# 3_3_5_12.net
KiCad netlist of a schematic drawn in EasyEDA Pro
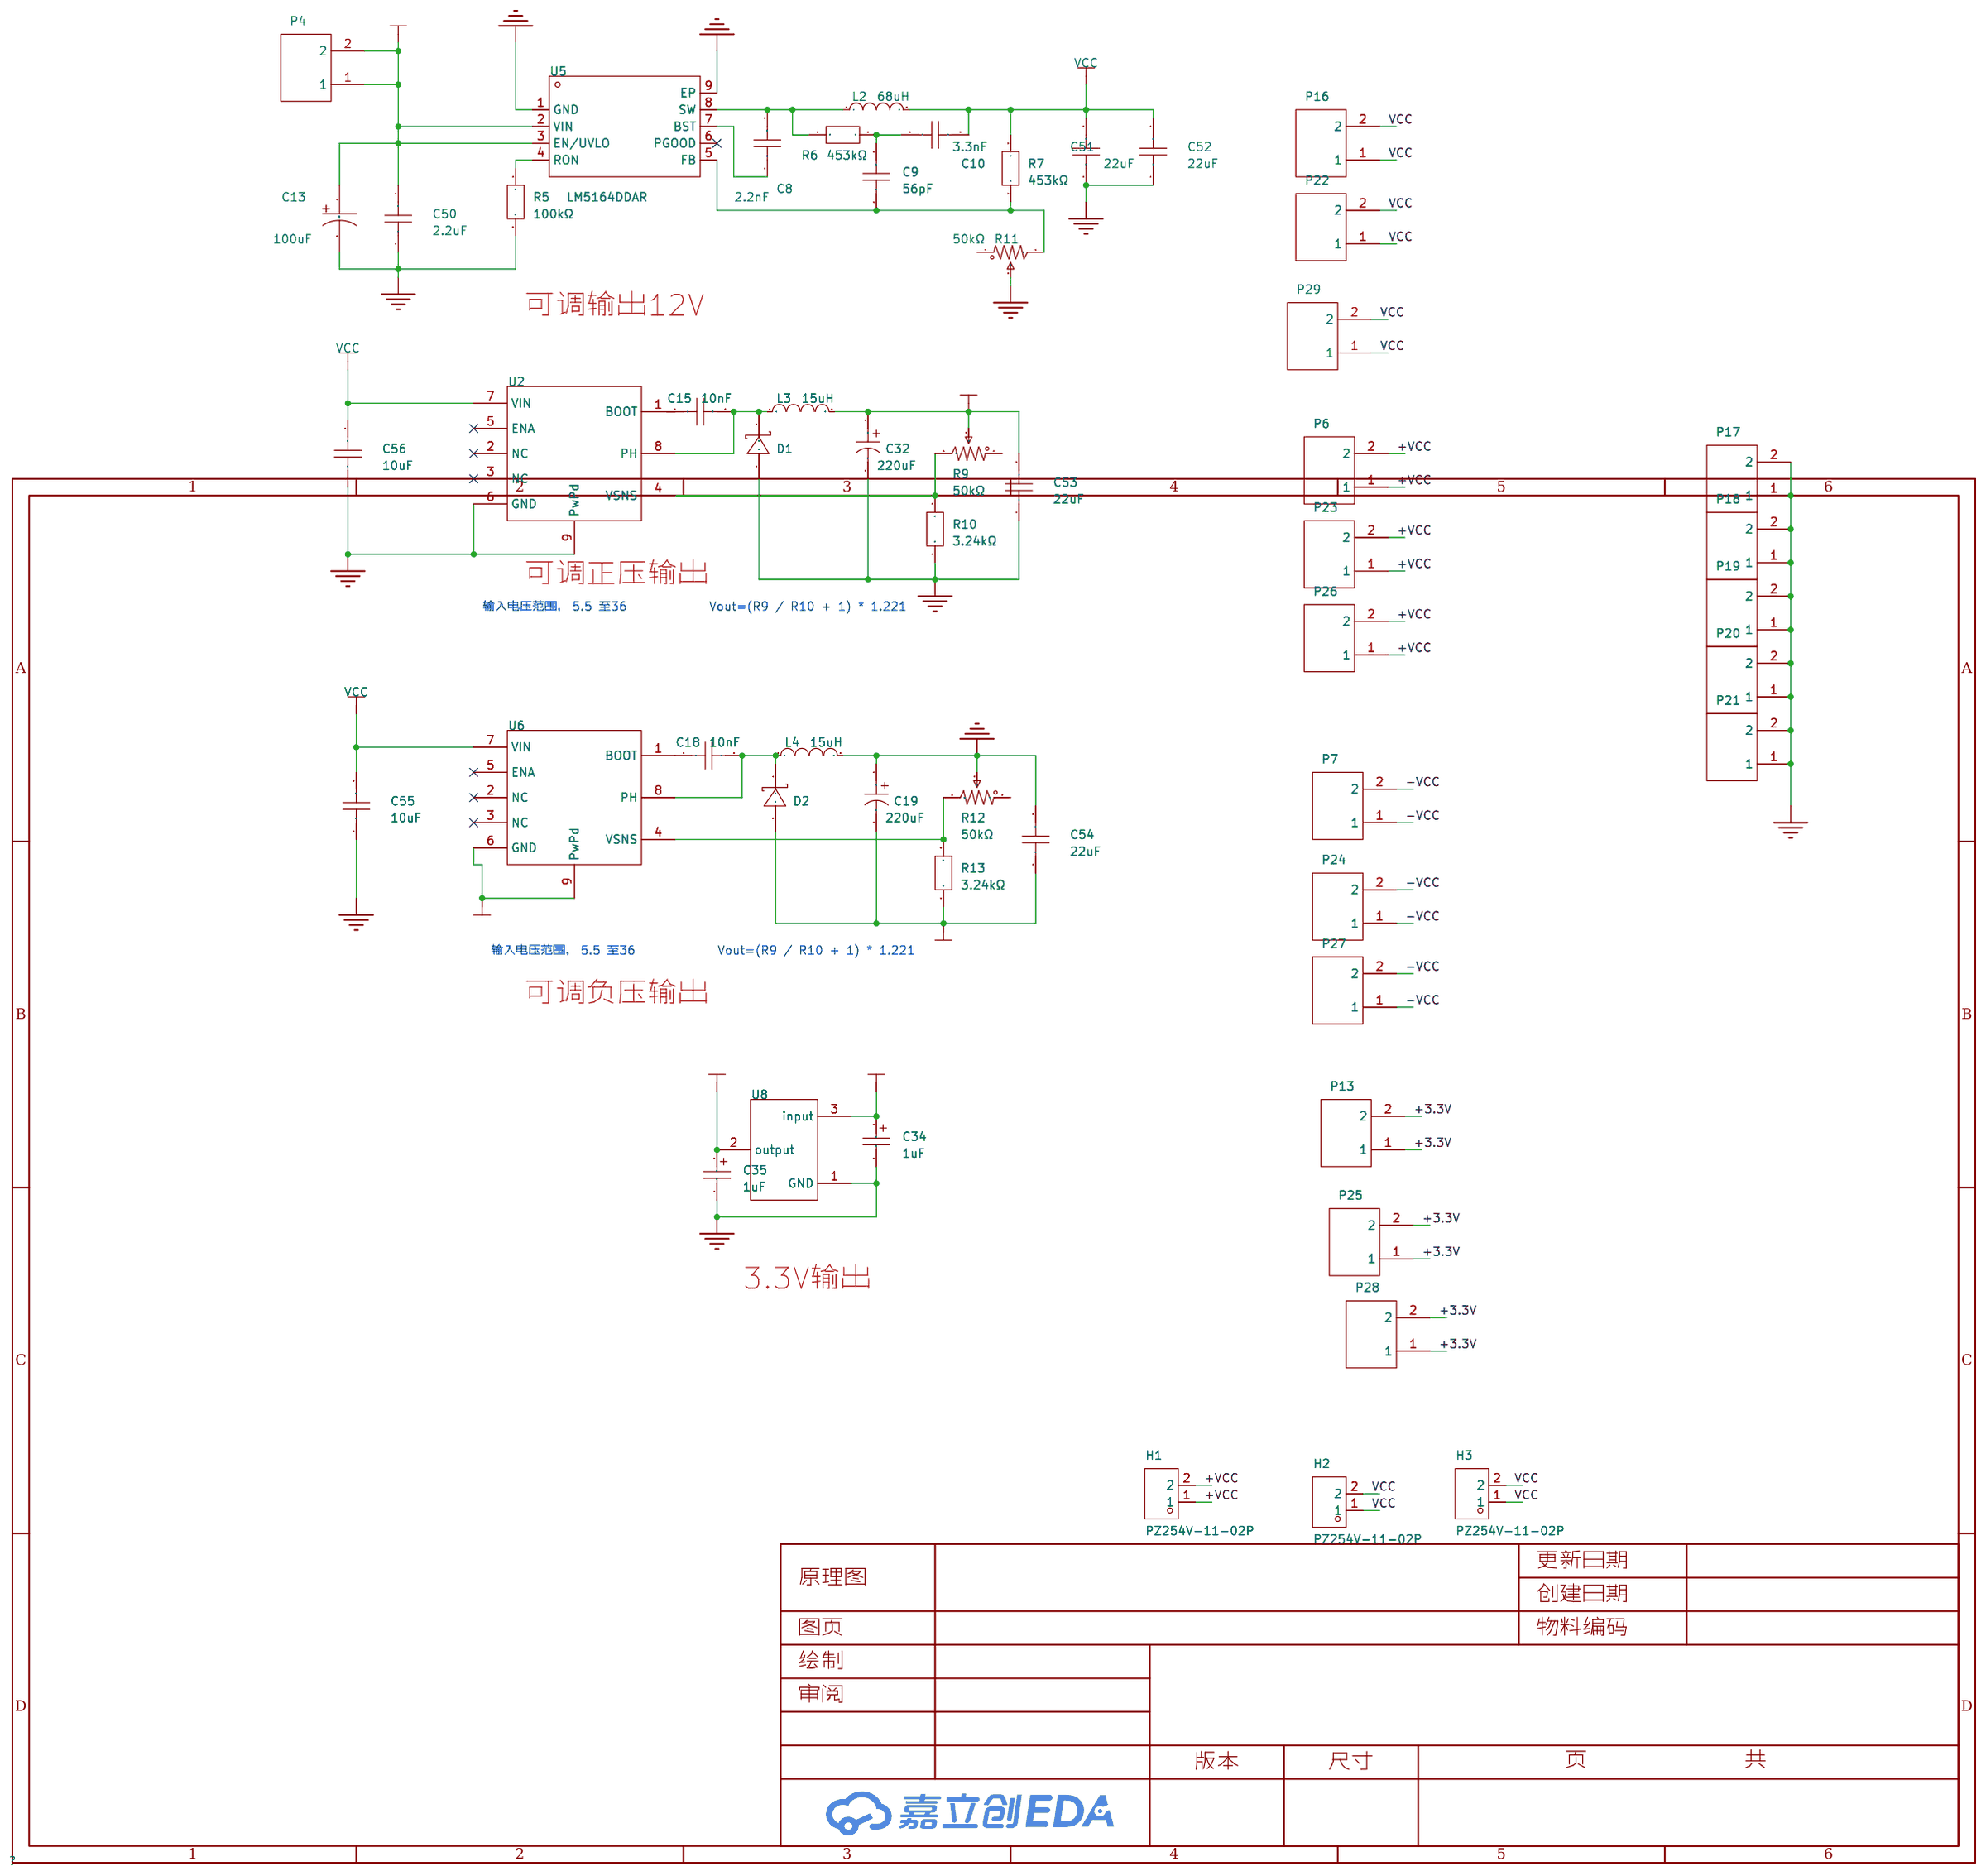
[diagram p0: schematic sheet]

(export (version "E")
  (design (tool "Eeschema 10.0.6"))
  (components
    (comp (ref "C8")
      (value "2.2nF")
      (footprint "easyedapro:C0805")
      (description "容值:2.2nF;精度:±5%;额定电压:250V;材质(温度系数):C0G;")
      (fields
        (field (name "Manufacturer Part") "C0805X222JAGACAUTO")
        (field (name "Manufacturer") "KEMET(基美)")
      )
      (libsource (lib "easyedapro") (part "C0805X222JAGACAUTO"))
    )
    (comp (ref "C9")
      (value "56pF")
      (footprint "easyedapro:C0805")
      (description "容值:56pF;精度:±5%;额定电压:250V;材质(温度系数):C0G;")
      (fields
        (field (name "Manufacturer Part") "GRM21A5C2E560JW01D")
        (field (name "Manufacturer") "muRata(村田)")
      )
      (libsource (lib "easyedapro") (part "GRM21A5C2E560JW01D"))
    )
    (comp (ref "C10")
      (value "3.3nF")
      (footprint "easyedapro:C0805")
      (description "容值:3.3nF;精度:±10%;额定电压:50V;材质(温度系数):X7R;")
      (fields
        (field (name "Manufacturer Part") "GRM216R71H332KA01D")
        (field (name "Manufacturer") "muRata(村田)")
      )
      (libsource (lib "easyedapro") (part "GRM216R71H332KA01D"))
    )
    (comp (ref "C13")
      (value "100uF")
      (footprint "easyedapro:CAP-TH_BD10.0-P5.00-D1.0-FD")
      (fields
        (field (name "Manufacturer Part") "RC100M101LO10*16TH-2A1E")
        (field (name "Manufacturer") "BERYL(绿宝石)")
      )
      (libsource (lib "easyedapro") (part "RC100M101LO10*16TH-2A1E"))
    )
    (comp (ref "C15")
      (value "10nF")
      (footprint "easyedapro:C0805")
      (description "容值:10nF;精度:±10%;额定电压:50V;材质(温度系数):X8R;")
      (fields (field (name "Manufacturer Part") "C0805C103K5HACTU") (field (name "Manufacturer") "KEMET(基美)"))
      (libsource (lib "easyedapro") (part "C0805C103K5HACTU"))
    )
    (comp (ref "C18")
      (value "10nF")
      (footprint "easyedapro:C0805")
      (description "容值:10nF;精度:±10%;额定电压:50V;材质(温度系数):X8R;")
      (fields (field (name "Manufacturer Part") "C0805C103K5HACTU") (field (name "Manufacturer") "KEMET(基美)"))
      (libsource (lib "easyedapro") (part "C0805C103K5HACTU"))
    )
    (comp (ref "C19")
      (value "220uF")
      (fields (field (name "Manufacturer Part") "ERE1VM221F12OT") (field (name "Manufacturer") "AISHI(艾华集团)"))
      (libsource (lib "easyedapro") (part "RVE100UF35V67RV0072"))
    )
    (comp (ref "C32")
      (value "220uF")
      (fields (field (name "Manufacturer Part") "ERE1VM221F12OT") (field (name "Manufacturer") "AISHI(艾华集团)"))
      (libsource (lib "easyedapro") (part "RVE100UF35V67RV0072"))
    )
    (comp (ref "C34")
      (value "1uF")
      (footprint "easyedapro:CASE-A_3216")
      (description "容值:1uF;精度:±10%;额定电压:35V;等效串联电阻:7.5Ω@100kHz;")
      (fields (field (name "Manufacturer Part") "TAJA105K035RNJ") (field (name "Manufacturer") "Kyocera AVX"))
      (libsource (lib "easyedapro") (part "TAJA105K035RNJ"))
    )
    (comp (ref "C35")
      (value "1uF")
      (footprint "easyedapro:CASE-A_3216")
      (description "容值:1uF;精度:±10%;额定电压:35V;等效串联电阻:7.5Ω@100kHz;")
      (fields (field (name "Manufacturer Part") "TAJA105K035RNJ") (field (name "Manufacturer") "Kyocera AVX"))
      (libsource (lib "easyedapro") (part "TAJA105K035RNJ"))
    )
    (comp (ref "C50")
      (value "2.2uF")
      (footprint "easyedapro:C0805")
      (description "容值:2.2uF;精度:±10%;额定电压:100V;材质(温度系数):X7R;")
      (fields
        (field (name "Manufacturer Part") "CGA0805X7R225K101MT")
        (field (name "Manufacturer") "HRE(芯声)")
      )
      (libsource (lib "easyedapro") (part "CGA0805X7R225K101MT"))
    )
    (comp (ref "C51")
      (value "22uF")
      (footprint "easyedapro:C0805")
      (description "容值:22uF;精度:±20%;额定电压:35V;材质(温度系数):X5R;")
      (fields
        (field (name "Manufacturer Part") "CGA0805X5R226M350MT")
        (field (name "Manufacturer") "HRE(芯声)")
      )
      (libsource (lib "easyedapro") (part "CGA0805X5R226M350MT"))
    )
    (comp (ref "C52")
      (value "22uF")
      (footprint "easyedapro:C0805")
      (description "容值:22uF;精度:±20%;额定电压:35V;材质(温度系数):X5R;")
      (fields
        (field (name "Manufacturer Part") "CGA0805X5R226M350MT")
        (field (name "Manufacturer") "HRE(芯声)")
      )
      (libsource (lib "easyedapro") (part "CGA0805X5R226M350MT"))
    )
    (comp (ref "C53")
      (value "22uF")
      (footprint "easyedapro:C0805")
      (description "容值:22uF;精度:±20%;额定电压:35V;材质(温度系数):X5R;")
      (fields
        (field (name "Manufacturer Part") "CGA0805X5R226M350MT")
        (field (name "Manufacturer") "HRE(芯声)")
      )
      (libsource (lib "easyedapro") (part "CGA0805X5R226M350MT"))
    )
    (comp (ref "C54")
      (value "22uF")
      (footprint "easyedapro:C0805")
      (description "容值:22uF;精度:±20%;额定电压:35V;材质(温度系数):X5R;")
      (fields
        (field (name "Manufacturer Part") "CGA0805X5R226M350MT")
        (field (name "Manufacturer") "HRE(芯声)")
      )
      (libsource (lib "easyedapro") (part "CGA0805X5R226M350MT"))
    )
    (comp (ref "C55")
      (value "10uF")
      (footprint "easyedapro:C0805")
      (description "容值:10uF;精度:±10%;额定电压:50V;材质(温度系数):X5R;")
      (fields
        (field (name "Manufacturer Part") "GRM21BR61H106KE43L")
        (field (name "Manufacturer") "muRata(村田)")
      )
      (libsource (lib "easyedapro") (part "GRM21BR61H106KE43L"))
    )
    (comp (ref "C56")
      (value "10uF")
      (footprint "easyedapro:C0805")
      (description "容值:10uF;精度:±10%;额定电压:50V;材质(温度系数):X5R;")
      (fields
        (field (name "Manufacturer Part") "GRM21BR61H106KE43L")
        (field (name "Manufacturer") "muRata(村田)")
      )
      (libsource (lib "easyedapro") (part "GRM21BR61H106KE43L"))
    )
    (comp (ref "D1")
      (value "B340A")
      (footprint "easyedapro:SMA_L4.3-W2.6-LS5.1-RD")
      (description "直流反向耐压(Vr):40V;平均整流电流(Io):3A;正向压降(Vf):550mV@3A;")
      (fields (field (name "Manufacturer") "MDD"))
      (libsource (lib "easyedapro") (part "B340A"))
    )
    (comp (ref "D2")
      (value "B340A")
      (footprint "easyedapro:SMA_L4.3-W2.6-LS5.1-RD")
      (description "直流反向耐压(Vr):40V;平均整流电流(Io):3A;正向压降(Vf):550mV@3A;")
      (fields (field (name "Manufacturer") "MDD"))
      (libsource (lib "easyedapro") (part "B340A"))
    )
    (comp (ref "H1")
      (value "PZ254V-11-02P")
      (footprint "easyedapro:HDR-TH_2P-P2.54-V-M")
      (fields (field (name "Manufacturer") "XFCN(兴飞)"))
      (libsource (lib "easyedapro") (part "PZ254V-11-02P"))
    )
    (comp (ref "H2")
      (value "PZ254V-11-02P")
      (footprint "easyedapro:HDR-TH_2P-P2.54-V-M")
      (fields (field (name "Manufacturer") "XFCN(兴飞)"))
      (libsource (lib "easyedapro") (part "PZ254V-11-02P"))
    )
    (comp (ref "H3")
      (value "PZ254V-11-02P")
      (footprint "easyedapro:HDR-TH_2P-P2.54-V-M")
      (fields (field (name "Manufacturer") "XFCN(兴飞)"))
      (libsource (lib "easyedapro") (part "PZ254V-11-02P"))
    )
    (comp (ref "L2")
      (value "68uH")
      (footprint "easyedapro:IND-SMD_L13.5-W12.8_APH1265T")
      (description "电感值:68uH;精度:±20%;额定电流:4.1A;饱和电流(Isat):4.3A;类型:一体成型电感;")
      (fields (field (name "Manufacturer Part") "APH1265T680M") (field (name "Manufacturer") "APV(爱普微)"))
      (libsource (lib "easyedapro") (part "APH1265T680M"))
    )
    (comp (ref "L3")
      (value "15uH")
      (footprint "easyedapro:IND-SMD_L7.3-W6.8")
      (description "精度:±20%;额定电流:3A;电感值:15uH;直流电阻(DCR):113mΩ;")
      (fields
        (field (name "Manufacturer Part") "MWSA0603S-150MT")
        (field (name "Manufacturer") "Sunlord(顺络)")
      )
      (libsource (lib "easyedapro") (part "MWSA0603S-150MT"))
    )
    (comp (ref "L4")
      (value "15uH")
      (footprint "easyedapro:IND-SMD_L7.3-W6.8")
      (description "精度:±20%;额定电流:3A;电感值:15uH;直流电阻(DCR):113mΩ;")
      (fields
        (field (name "Manufacturer Part") "MWSA0603S-150MT")
        (field (name "Manufacturer") "Sunlord(顺络)")
      )
      (libsource (lib "easyedapro") (part "MWSA0603S-150MT"))
    )
    (comp (ref "P4")
      (value "WJ128V-5.0-2P")
      (footprint "easyedapro:CONN-TH_2P-P5.00_WJ128V-5.0-2P")
      (fields (field (name "Manufacturer") "KANGNEX(康奈克斯电气)"))
      (libsource (lib "easyedapro") (part "WJ128V-5.0-2P"))
    )
    (comp (ref "P6")
      (value "WJ128V-5.0-2P")
      (footprint "easyedapro:CONN-TH_2P-P5.00_WJ128V-5.0-2P")
      (fields (field (name "Manufacturer") "KANGNEX(康奈克斯电气)"))
      (libsource (lib "easyedapro") (part "WJ128V-5.0-2P"))
    )
    (comp (ref "P7")
      (value "WJ128V-5.0-2P")
      (footprint "easyedapro:CONN-TH_2P-P5.00_WJ128V-5.0-2P")
      (fields (field (name "Manufacturer") "KANGNEX(康奈克斯电气)"))
      (libsource (lib "easyedapro") (part "WJ128V-5.0-2P"))
    )
    (comp (ref "P13")
      (value "WJ128V-5.0-2P")
      (footprint "easyedapro:CONN-TH_2P-P5.00_WJ128V-5.0-2P")
      (fields (field (name "Manufacturer") "KANGNEX(康奈克斯电气)"))
      (libsource (lib "easyedapro") (part "WJ128V-5.0-2P"))
    )
    (comp (ref "P16")
      (value "WJ128V-5.0-2P")
      (footprint "easyedapro:CONN-TH_2P-P5.00_WJ128V-5.0-2P")
      (fields (field (name "Manufacturer") "KANGNEX(康奈克斯电气)"))
      (libsource (lib "easyedapro") (part "WJ128V-5.0-2P"))
    )
    (comp (ref "P17")
      (value "WJ128V-5.0-2P")
      (footprint "easyedapro:CONN-TH_2P-P5.00_WJ128V-5.0-2P")
      (fields (field (name "Manufacturer") "KANGNEX(康奈克斯电气)"))
      (libsource (lib "easyedapro") (part "WJ128V-5.0-2P"))
    )
    (comp (ref "P18")
      (value "WJ128V-5.0-2P")
      (footprint "easyedapro:CONN-TH_2P-P5.00_WJ128V-5.0-2P")
      (fields (field (name "Manufacturer") "KANGNEX(康奈克斯电气)"))
      (libsource (lib "easyedapro") (part "WJ128V-5.0-2P"))
    )
    (comp (ref "P19")
      (value "WJ128V-5.0-2P")
      (footprint "easyedapro:CONN-TH_2P-P5.00_WJ128V-5.0-2P")
      (fields (field (name "Manufacturer") "KANGNEX(康奈克斯电气)"))
      (libsource (lib "easyedapro") (part "WJ128V-5.0-2P"))
    )
    (comp (ref "P20")
      (value "WJ128V-5.0-2P")
      (footprint "easyedapro:CONN-TH_2P-P5.00_WJ128V-5.0-2P")
      (fields (field (name "Manufacturer") "KANGNEX(康奈克斯电气)"))
      (libsource (lib "easyedapro") (part "WJ128V-5.0-2P"))
    )
    (comp (ref "P21")
      (value "WJ128V-5.0-2P")
      (footprint "easyedapro:CONN-TH_2P-P5.00_WJ128V-5.0-2P")
      (fields (field (name "Manufacturer") "KANGNEX(康奈克斯电气)"))
      (libsource (lib "easyedapro") (part "WJ128V-5.0-2P"))
    )
    (comp (ref "P22")
      (value "WJ128V-5.0-2P")
      (footprint "easyedapro:CONN-TH_2P-P5.00_WJ128V-5.0-2P")
      (fields (field (name "Manufacturer") "KANGNEX(康奈克斯电气)"))
      (libsource (lib "easyedapro") (part "WJ128V-5.0-2P"))
    )
    (comp (ref "P23")
      (value "WJ128V-5.0-2P")
      (footprint "easyedapro:CONN-TH_2P-P5.00_WJ128V-5.0-2P")
      (fields (field (name "Manufacturer") "KANGNEX(康奈克斯电气)"))
      (libsource (lib "easyedapro") (part "WJ128V-5.0-2P"))
    )
    (comp (ref "P24")
      (value "WJ128V-5.0-2P")
      (footprint "easyedapro:CONN-TH_2P-P5.00_WJ128V-5.0-2P")
      (fields (field (name "Manufacturer") "KANGNEX(康奈克斯电气)"))
      (libsource (lib "easyedapro") (part "WJ128V-5.0-2P"))
    )
    (comp (ref "P25")
      (value "WJ128V-5.0-2P")
      (footprint "easyedapro:CONN-TH_2P-P5.00_WJ128V-5.0-2P")
      (fields (field (name "Manufacturer") "KANGNEX(康奈克斯电气)"))
      (libsource (lib "easyedapro") (part "WJ128V-5.0-2P"))
    )
    (comp (ref "P26")
      (value "WJ128V-5.0-2P")
      (footprint "easyedapro:CONN-TH_2P-P5.00_WJ128V-5.0-2P")
      (fields (field (name "Manufacturer") "KANGNEX(康奈克斯电气)"))
      (libsource (lib "easyedapro") (part "WJ128V-5.0-2P"))
    )
    (comp (ref "P27")
      (value "WJ128V-5.0-2P")
      (footprint "easyedapro:CONN-TH_2P-P5.00_WJ128V-5.0-2P")
      (fields (field (name "Manufacturer") "KANGNEX(康奈克斯电气)"))
      (libsource (lib "easyedapro") (part "WJ128V-5.0-2P"))
    )
    (comp (ref "P28")
      (value "WJ128V-5.0-2P")
      (footprint "easyedapro:CONN-TH_2P-P5.00_WJ128V-5.0-2P")
      (fields (field (name "Manufacturer") "KANGNEX(康奈克斯电气)"))
      (libsource (lib "easyedapro") (part "WJ128V-5.0-2P"))
    )
    (comp (ref "P29")
      (value "WJ128V-5.0-2P")
      (footprint "easyedapro:CONN-TH_2P-P5.00_WJ128V-5.0-2P")
      (fields (field (name "Manufacturer") "KANGNEX(康奈克斯电气)"))
      (libsource (lib "easyedapro") (part "WJ128V-5.0-2P"))
    )
    (comp (ref "R5")
      (value "100kΩ")
      (footprint "easyedapro:R0805")
      (description "电阻类型:薄膜电阻;阻值:100kΩ;精度:±0.01%;温度系数:±5ppm/°C;")
      (fields
        (field (name "Manufacturer Part") "TP0805T100KP0505Z")
        (field (name "Manufacturer") "EVER OHMS(天二科技)")
      )
      (libsource (lib "easyedapro") (part "TP0805T100KP0505Z"))
    )
    (comp (ref "R6")
      (value "453kΩ")
      (footprint "easyedapro:R0805")
      (description "电阻类型:薄膜电阻;阻值:100kΩ;精度:±0.01%;温度系数:±5ppm/°C;")
      (fields
        (field (name "Manufacturer Part") "TP0805T100KP0505Z")
        (field (name "Manufacturer") "EVER OHMS(天二科技)")
      )
      (libsource (lib "easyedapro") (part "TP0805T100KP0505Z"))
    )
    (comp (ref "R7")
      (value "453kΩ")
      (footprint "easyedapro:R0805")
      (description "电阻类型:薄膜电阻;阻值:453kΩ;精度:±0.5%;功率:100mW;最大工作电压:100V;温度系数:±25ppm/°C;")
      (fields (field (name "Manufacturer Part") "RR1220P-4533-D-M") (field (name "Manufacturer") "SUSUMU"))
      (libsource (lib "easyedapro") (part "RR1220P-4533-D-M"))
    )
    (comp (ref "R9")
      (value "50kΩ")
      (fields (field (name "Manufacturer Part") "3296W-1-503") (field (name "Manufacturer") "BOCHEN(博晨)"))
      (libsource (lib "easyedapro") (part "3296W-1-103"))
    )
    (comp (ref "R10")
      (value "3.24kΩ")
      (footprint "easyedapro:R0805")
      (description "阻值:3.24kΩ;精度:±1%;功率:125mW;")
      (fields (field (name "Manufacturer Part") "RCA053K24FLF") (field (name "Manufacturer") "HKR(香港电阻)"))
      (libsource (lib "easyedapro") (part "RCA053K24FLF"))
    )
    (comp (ref "R11")
      (value "50kΩ")
      (fields (field (name "Manufacturer Part") "3296W-1-503") (field (name "Manufacturer") "BOCHEN(博晨)"))
      (libsource (lib "easyedapro") (part "3296W-1-103"))
    )
    (comp (ref "R12")
      (value "50kΩ")
      (fields (field (name "Manufacturer Part") "3296W-1-503") (field (name "Manufacturer") "BOCHEN(博晨)"))
      (libsource (lib "easyedapro") (part "3296W-1-103"))
    )
    (comp (ref "R13")
      (value "3.24kΩ")
      (footprint "easyedapro:R0805")
      (description "阻值:3.24kΩ;精度:±1%;功率:125mW;")
      (fields (field (name "Manufacturer Part") "RCA053K24FLF") (field (name "Manufacturer") "HKR(香港电阻)"))
      (libsource (lib "easyedapro") (part "RCA053K24FLF"))
    )
    (comp (ref "U2")
      (value "TPS5430DDAR")
      (footprint "easyedapro:ESOP-8_L4.9-W3.9-P1.27-LS6.0-TL-EP")
      (description "功能类型:降压型;同步整流:-;输出通道数:-;拓扑结构:-;输入电压:-;输出电流(最大值):-;开关频率:-;")
      (fields (field (name "Manufacturer") "TI(德州仪器)"))
      (libsource (lib "easyedapro") (part "TPS5430DDAR"))
    )
    (comp (ref "U5")
      (value "LM5164DDAR")
      (footprint "easyedapro:SO-8_L4.9-W3.9-P1.27-LS6.0-BL-EP")
      (description "功能类型:降压型;输出类型:可调;输入电压:6V~100V;输出电压:1.2V~100V;输出电流(最大值):1A;")
      (fields (field (name "Manufacturer") "TI(德州仪器)"))
      (libsource (lib "easyedapro") (part "LM5164DDAR"))
    )
    (comp (ref "U6")
      (value "TPS5430DDAR")
      (footprint "easyedapro:ESOP-8_L4.9-W3.9-P1.27-LS6.0-TL-EP")
      (description "功能类型:降压型;同步整流:-;输出通道数:-;拓扑结构:-;输入电压:-;输出电流(最大值):-;开关频率:-;")
      (fields (field (name "Manufacturer") "TI(德州仪器)"))
      (libsource (lib "easyedapro") (part "TPS5430DDAR"))
    )
    (comp (ref "U8")
      (value "ME6206A33M3G")
      (footprint "easyedapro:SOT-23-3_L2.9-W1.6-P1.90-LS2.8-BR")
      (description "输出类型:固定;输出极性:正;最大输入电压:6V;输出电压:3.3V;输出电流:300mA;电源纹波抑制比(PSRR):50dB@(1kHz);")
      (fields (field (name "Manufacturer") "MICRONE(南京微盟)"))
      (libsource (lib "easyedapro") (part "ME6206A33M3G"))
    )
  )
  (nets
    (net (code "1") (name "+3.3V") (class "Default")
      (node (ref "C35") (pin "1") (pinfunction "1_1") (pintype "input"))
      (node (ref "P13") (pin "1") (pinfunction "1_1") (pintype "unspecified"))
      (node (ref "P13") (pin "2") (pinfunction "2_2") (pintype "unspecified"))
      (node (ref "P25") (pin "1") (pinfunction "1_1") (pintype "unspecified"))
      (node (ref "P25") (pin "2") (pinfunction "2_2") (pintype "unspecified"))
      (node (ref "P28") (pin "1") (pinfunction "1_1") (pintype "unspecified"))
      (node (ref "P28") (pin "2") (pinfunction "2_2") (pintype "unspecified"))
      (node (ref "U8") (pin "2") (pinfunction "output_2") (pintype "input"))
    )
    (net (code "2") (name "+VCC") (class "Default")
      (node (ref "C32") (pin "1") (pinfunction "1_1") (pintype "input"))
      (node (ref "C34") (pin "1") (pinfunction "1_1") (pintype "input"))
      (node (ref "C53") (pin "2") (pinfunction "2_2") (pintype "unspecified"))
      (node (ref "H1") (pin "1") (pinfunction "1_1") (pintype "unspecified"))
      (node (ref "H1") (pin "2") (pinfunction "2_2") (pintype "unspecified"))
      (node (ref "L3") (pin "2") (pinfunction "2_2") (pintype "input"))
      (node (ref "P23") (pin "1") (pinfunction "1_1") (pintype "unspecified"))
      (node (ref "P23") (pin "2") (pinfunction "2_2") (pintype "unspecified"))
      (node (ref "P26") (pin "1") (pinfunction "1_1") (pintype "unspecified"))
      (node (ref "P26") (pin "2") (pinfunction "2_2") (pintype "unspecified"))
      (node (ref "P6") (pin "1") (pinfunction "1_1") (pintype "unspecified"))
      (node (ref "P6") (pin "2") (pinfunction "2_2") (pintype "unspecified"))
      (node (ref "R9") (pin "2") (pinfunction "2_2") (pintype "input"))
      (node (ref "U8") (pin "3") (pinfunction "input_3") (pintype "input"))
    )
    (net (code "3") (name "-VCC") (class "Default")
      (node (ref "C19") (pin "2") (pinfunction "2_2") (pintype "input"))
      (node (ref "C54") (pin "1") (pinfunction "1_1") (pintype "unspecified"))
      (node (ref "D2") (pin "2") (pinfunction "A_2") (pintype "input"))
      (node (ref "P24") (pin "1") (pinfunction "1_1") (pintype "unspecified"))
      (node (ref "P24") (pin "2") (pinfunction "2_2") (pintype "unspecified"))
      (node (ref "P27") (pin "1") (pinfunction "1_1") (pintype "unspecified"))
      (node (ref "P27") (pin "2") (pinfunction "2_2") (pintype "unspecified"))
      (node (ref "P7") (pin "1") (pinfunction "1_1") (pintype "unspecified"))
      (node (ref "P7") (pin "2") (pinfunction "2_2") (pintype "unspecified"))
      (node (ref "R13") (pin "1") (pinfunction "1_1") (pintype "unspecified"))
      (node (ref "U6") (pin "6") (pinfunction "GND_6") (pintype "input"))
      (node (ref "U6") (pin "9") (pinfunction "PwPd_9") (pintype "input"))
    )
    (net (code "4") (name "GND") (class "Default")
      (node (ref "C13") (pin "2") (pinfunction "2_2") (pintype "input"))
      (node (ref "C19") (pin "1") (pinfunction "1_1") (pintype "input"))
      (node (ref "C32") (pin "2") (pinfunction "2_2") (pintype "input"))
      (node (ref "C34") (pin "2") (pinfunction "2_2") (pintype "input"))
      (node (ref "C35") (pin "2") (pinfunction "2_2") (pintype "input"))
      (node (ref "C50") (pin "1") (pinfunction "1_1") (pintype "unspecified"))
      (node (ref "C51") (pin "1") (pinfunction "1_1") (pintype "unspecified"))
      (node (ref "C52") (pin "1") (pinfunction "1_1") (pintype "unspecified"))
      (node (ref "C53") (pin "1") (pinfunction "1_1") (pintype "unspecified"))
      (node (ref "C54") (pin "2") (pinfunction "2_2") (pintype "unspecified"))
      (node (ref "C55") (pin "1") (pinfunction "1_1") (pintype "unspecified"))
      (node (ref "C56") (pin "1") (pinfunction "1_1") (pintype "unspecified"))
      (node (ref "D1") (pin "2") (pinfunction "A_2") (pintype "input"))
      (node (ref "L4") (pin "2") (pinfunction "2_2") (pintype "input"))
      (node (ref "P17") (pin "1") (pinfunction "1_1") (pintype "unspecified"))
      (node (ref "P17") (pin "2") (pinfunction "2_2") (pintype "unspecified"))
      (node (ref "P18") (pin "1") (pinfunction "1_1") (pintype "unspecified"))
      (node (ref "P18") (pin "2") (pinfunction "2_2") (pintype "unspecified"))
      (node (ref "P19") (pin "1") (pinfunction "1_1") (pintype "unspecified"))
      (node (ref "P19") (pin "2") (pinfunction "2_2") (pintype "unspecified"))
      (node (ref "P20") (pin "1") (pinfunction "1_1") (pintype "unspecified"))
      (node (ref "P20") (pin "2") (pinfunction "2_2") (pintype "unspecified"))
      (node (ref "P21") (pin "1") (pinfunction "1_1") (pintype "unspecified"))
      (node (ref "P21") (pin "2") (pinfunction "2_2") (pintype "unspecified"))
      (node (ref "R10") (pin "1") (pinfunction "1_1") (pintype "unspecified"))
      (node (ref "R11") (pin "2") (pinfunction "2_2") (pintype "input"))
      (node (ref "R12") (pin "2") (pinfunction "2_2") (pintype "input"))
      (node (ref "R5") (pin "2") (pinfunction "2_2") (pintype "unspecified"))
      (node (ref "U2") (pin "6") (pinfunction "GND_6") (pintype "input"))
      (node (ref "U2") (pin "9") (pinfunction "PwPd_9") (pintype "input"))
      (node (ref "U5") (pin "1") (pinfunction "GND_1") (pintype "input"))
      (node (ref "U5") (pin "9") (pinfunction "EP_9") (pintype "input"))
      (node (ref "U8") (pin "1") (pinfunction "GND_1") (pintype "input"))
    )
    (net (code "5") (name "Net-(C10-Pad1)") (class "Default")
      (node (ref "C10") (pin "1") (pinfunction "1_1") (pintype "unspecified"))
      (node (ref "C9") (pin "2") (pinfunction "2_2") (pintype "unspecified"))
      (node (ref "R6") (pin "1") (pinfunction "1_1") (pintype "unspecified"))
    )
    (net (code "6") (name "Net-(D1-K)") (class "Default")
      (node (ref "C15") (pin "2") (pinfunction "2_2") (pintype "unspecified"))
      (node (ref "D1") (pin "1") (pinfunction "K_1") (pintype "input"))
      (node (ref "L3") (pin "1") (pinfunction "1_1") (pintype "input"))
      (node (ref "U2") (pin "8") (pinfunction "PH_8") (pintype "input"))
    )
    (net (code "7") (name "Net-(D2-K)") (class "Default")
      (node (ref "C18") (pin "2") (pinfunction "2_2") (pintype "unspecified"))
      (node (ref "D2") (pin "1") (pinfunction "K_1") (pintype "input"))
      (node (ref "L4") (pin "1") (pinfunction "1_1") (pintype "input"))
      (node (ref "U6") (pin "8") (pinfunction "PH_8") (pintype "input"))
    )
    (net (code "8") (name "Net-(U2-BOOT)") (class "Default")
      (node (ref "C15") (pin "1") (pinfunction "1_1") (pintype "unspecified"))
      (node (ref "U2") (pin "1") (pinfunction "BOOT_1") (pintype "input"))
    )
    (net (code "9") (name "Net-(U2-VSNS)") (class "Default")
      (node (ref "R10") (pin "2") (pinfunction "2_2") (pintype "unspecified"))
      (node (ref "R9") (pin "3") (pinfunction "3_3") (pintype "input"))
      (node (ref "U2") (pin "4") (pinfunction "VSNS_4") (pintype "input"))
    )
    (net (code "10") (name "Net-(U5-BST)") (class "Default")
      (node (ref "C8") (pin "1") (pinfunction "1_1") (pintype "unspecified"))
      (node (ref "U5") (pin "7") (pinfunction "BST_7") (pintype "input"))
    )
    (net (code "11") (name "Net-(U5-FB)") (class "Default")
      (node (ref "C9") (pin "1") (pinfunction "1_1") (pintype "unspecified"))
      (node (ref "R11") (pin "3") (pinfunction "3_3") (pintype "input"))
      (node (ref "R7") (pin "1") (pinfunction "1_1") (pintype "unspecified"))
      (node (ref "U5") (pin "5") (pinfunction "FB_5") (pintype "input"))
    )
    (net (code "12") (name "Net-(U5-RON)") (class "Default")
      (node (ref "R5") (pin "1") (pinfunction "1_1") (pintype "unspecified"))
      (node (ref "U5") (pin "4") (pinfunction "RON_4") (pintype "input"))
    )
    (net (code "13") (name "Net-(U5-SW)") (class "Default")
      (node (ref "C8") (pin "2") (pinfunction "2_2") (pintype "unspecified"))
      (node (ref "L2") (pin "1") (pinfunction "1_1") (pintype "unspecified"))
      (node (ref "R6") (pin "2") (pinfunction "2_2") (pintype "unspecified"))
      (node (ref "U5") (pin "8") (pinfunction "SW_8") (pintype "input"))
    )
    (net (code "14") (name "Net-(U6-BOOT)") (class "Default")
      (node (ref "C18") (pin "1") (pinfunction "1_1") (pintype "unspecified"))
      (node (ref "U6") (pin "1") (pinfunction "BOOT_1") (pintype "input"))
    )
    (net (code "15") (name "Net-(U6-VSNS)") (class "Default")
      (node (ref "R12") (pin "3") (pinfunction "3_3") (pintype "input"))
      (node (ref "R13") (pin "2") (pinfunction "2_2") (pintype "unspecified"))
      (node (ref "U6") (pin "4") (pinfunction "VSNS_4") (pintype "input"))
    )
    (net (code "16") (name "VCC") (class "Default")
      (node (ref "C10") (pin "2") (pinfunction "2_2") (pintype "unspecified"))
      (node (ref "C51") (pin "2") (pinfunction "2_2") (pintype "unspecified"))
      (node (ref "C52") (pin "2") (pinfunction "2_2") (pintype "unspecified"))
      (node (ref "C55") (pin "2") (pinfunction "2_2") (pintype "unspecified"))
      (node (ref "C56") (pin "2") (pinfunction "2_2") (pintype "unspecified"))
      (node (ref "H2") (pin "1") (pinfunction "1_1") (pintype "unspecified"))
      (node (ref "H2") (pin "2") (pinfunction "2_2") (pintype "unspecified"))
      (node (ref "H3") (pin "1") (pinfunction "1_1") (pintype "unspecified"))
      (node (ref "H3") (pin "2") (pinfunction "2_2") (pintype "unspecified"))
      (node (ref "L2") (pin "2") (pinfunction "2_2") (pintype "unspecified"))
      (node (ref "P16") (pin "1") (pinfunction "1_1") (pintype "unspecified"))
      (node (ref "P16") (pin "2") (pinfunction "2_2") (pintype "unspecified"))
      (node (ref "P22") (pin "1") (pinfunction "1_1") (pintype "unspecified"))
      (node (ref "P22") (pin "2") (pinfunction "2_2") (pintype "unspecified"))
      (node (ref "P29") (pin "1") (pinfunction "1_1") (pintype "unspecified"))
      (node (ref "P29") (pin "2") (pinfunction "2_2") (pintype "unspecified"))
      (node (ref "R7") (pin "2") (pinfunction "2_2") (pintype "unspecified"))
      (node (ref "U2") (pin "7") (pinfunction "VIN_7") (pintype "input"))
      (node (ref "U6") (pin "7") (pinfunction "VIN_7") (pintype "input"))
    )
    (net (code "17") (name "VIN") (class "Default")
      (node (ref "C13") (pin "1") (pinfunction "1_1") (pintype "input"))
      (node (ref "C50") (pin "2") (pinfunction "2_2") (pintype "unspecified"))
      (node (ref "P4") (pin "1") (pinfunction "1_1") (pintype "unspecified"))
      (node (ref "P4") (pin "2") (pinfunction "2_2") (pintype "unspecified"))
      (node (ref "U5") (pin "2") (pinfunction "VIN_2") (pintype "input"))
      (node (ref "U5") (pin "3") (pinfunction "EN/UVLO_3") (pintype "input"))
    )
    (net (code "18") (name "unconnected-(R9-Pad1)") (class "Default")
      (node (ref "R9") (pin "1") (pinfunction "1_1") (pintype "input"))
    )
    (net (code "19") (name "unconnected-(R11-Pad1)") (class "Default")
      (node (ref "R11") (pin "1") (pinfunction "1_1") (pintype "input"))
    )
    (net (code "20") (name "unconnected-(R12-Pad1)") (class "Default")
      (node (ref "R12") (pin "1") (pinfunction "1_1") (pintype "input"))
    )
    (net (code "21") (name "unconnected-(U2-ENA-Pad5)") (class "Default")
      (node (ref "U2") (pin "5") (pinfunction "ENA_5") (pintype "input+no_connect"))
    )
    (net (code "22") (name "unconnected-(U2-NC-Pad2)") (class "Default")
      (node (ref "U2") (pin "2") (pinfunction "NC_2") (pintype "input+no_connect"))
    )
    (net (code "23") (name "unconnected-(U2-NC-Pad3)") (class "Default")
      (node (ref "U2") (pin "3") (pinfunction "NC_3") (pintype "input+no_connect"))
    )
    (net (code "24") (name "unconnected-(U5-PGOOD-Pad6)") (class "Default")
      (node (ref "U5") (pin "6") (pinfunction "PGOOD_6") (pintype "input+no_connect"))
    )
    (net (code "25") (name "unconnected-(U6-ENA-Pad5)") (class "Default")
      (node (ref "U6") (pin "5") (pinfunction "ENA_5") (pintype "input+no_connect"))
    )
    (net (code "26") (name "unconnected-(U6-NC-Pad2)") (class "Default")
      (node (ref "U6") (pin "2") (pinfunction "NC_2") (pintype "input+no_connect"))
    )
    (net (code "27") (name "unconnected-(U6-NC-Pad3)") (class "Default")
      (node (ref "U6") (pin "3") (pinfunction "NC_3") (pintype "input+no_connect"))
    )
  )
)
